# Pwrmon.net
KiCad netlist of a schematic drawn in EAGLE
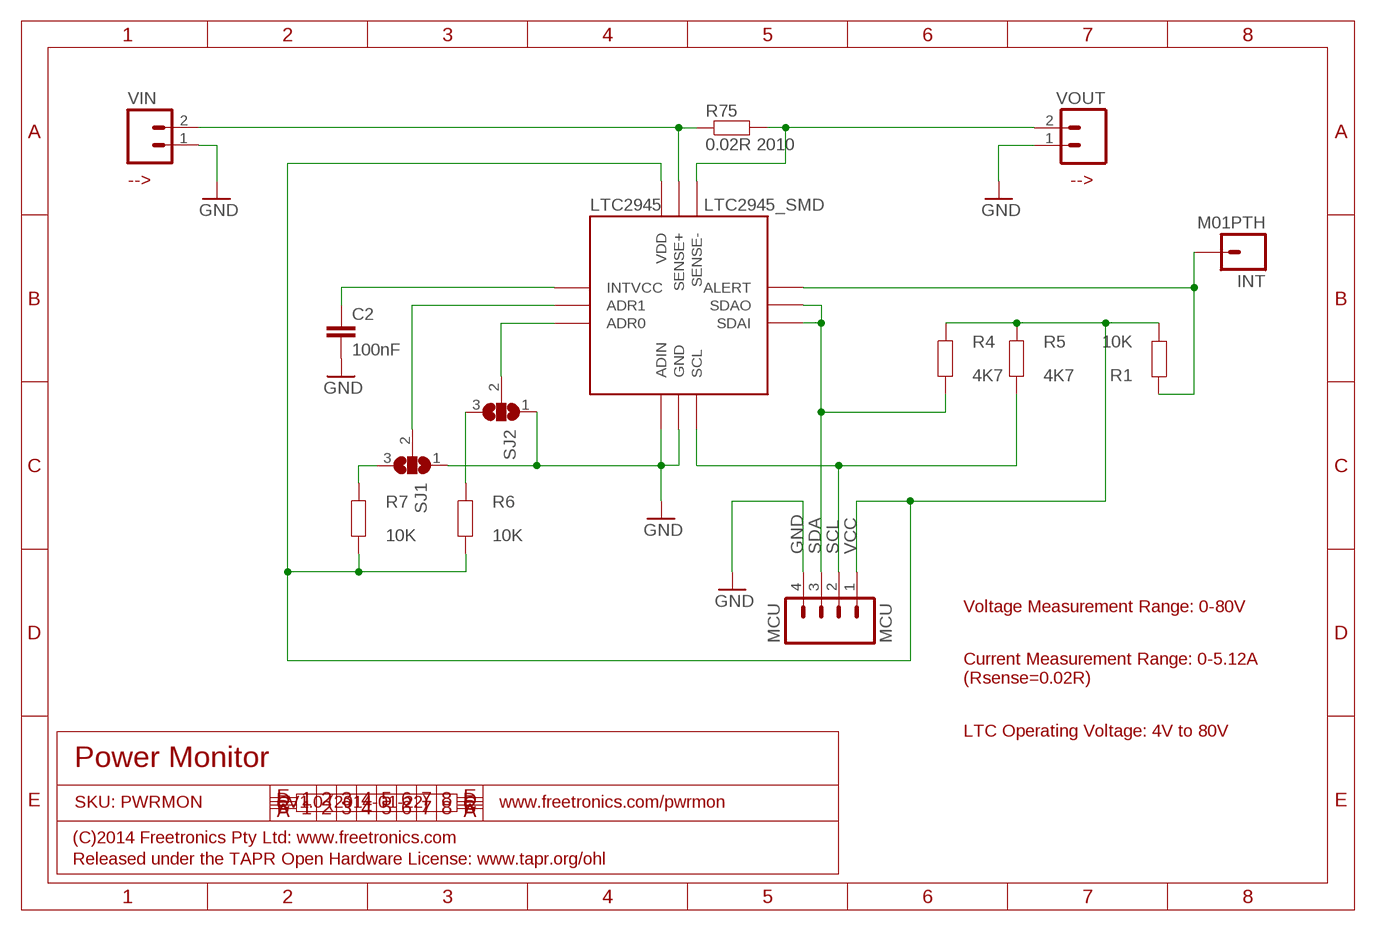
[diagram p0: schematic, sheet 1]

(export (version "E")
  (design (tool "Eeschema 10.0.6"))
  (components
    (comp (ref "C2")
      (value "100nF")
      (footprint "eagle-import:0603")
      (libsource (lib "eagle-import") (part "CAP0603"))
    )
    (comp (ref "INT")
      (value "M01PTH")
      (footprint "eagle-import:1X01")
      (libsource (lib "eagle-import") (part "M01PTH"))
    )
    (comp (ref "LTC2945")
      (value "LTC2945_SMD")
      (footprint "eagle-import:QFN-12")
      (libsource (lib "eagle-import") (part "LTC2945_SMD"))
    )
    (comp (ref "MCU")
      (value "MCU")
      (footprint "eagle-import:1X04")
      (libsource (lib "eagle-import") (part "M04PTH"))
    )
    (comp (ref "R1")
      (value "10K")
      (footprint "eagle-import:0603")
      (libsource (lib "eagle-import") (part "RESISTOR0603"))
    )
    (comp (ref "R4")
      (value "4K7")
      (footprint "eagle-import:0603")
      (libsource (lib "eagle-import") (part "RESISTOR0603"))
    )
    (comp (ref "R5")
      (value "4K7")
      (footprint "eagle-import:0603")
      (libsource (lib "eagle-import") (part "RESISTOR0603"))
    )
    (comp (ref "R6")
      (value "10K")
      (footprint "eagle-import:0603")
      (libsource (lib "eagle-import") (part "RESISTOR0603"))
    )
    (comp (ref "R7")
      (value "10K")
      (footprint "eagle-import:0603")
      (libsource (lib "eagle-import") (part "RESISTOR0603"))
    )
    (comp (ref "R75")
      (value "0.02R 2010")
      (footprint "eagle-import:R2010")
      (libsource (lib "eagle-import") (part "freetronics-original_RESISTOR2010"))
    )
    (comp (ref "SJ1")
      (value "SJ2W")
      (footprint "eagle-import:SJ_2")
      (libsource (lib "eagle-import") (part "SJ2W"))
    )
    (comp (ref "SJ2")
      (value "SJ2W")
      (footprint "eagle-import:SJ_2")
      (libsource (lib "eagle-import") (part "SJ2W"))
    )
    (comp (ref "VIN")
      (value "M02PTH")
      (footprint "eagle-import:1X02")
      (libsource (lib "eagle-import") (part "M02PTH"))
    )
    (comp (ref "VOUT")
      (value "M02PTH")
      (footprint "eagle-import:1X02")
      (libsource (lib "eagle-import") (part "M02PTH"))
    )
  )
  (nets
    (net (code "1") (name "/SCL") (class "Default")
      (node (ref "LTC2945") (pin "6") (pinfunction "SCL_6") (pintype "bidirectional"))
      (node (ref "MCU") (pin "2") (pinfunction "2_2") (pintype "passive"))
      (node (ref "R5") (pin "1") (pinfunction "1_1") (pintype "passive"))
    )
    (net (code "2") (name "/SDA") (class "Default")
      (node (ref "LTC2945") (pin "7") (pinfunction "SDAI_7") (pintype "bidirectional"))
      (node (ref "LTC2945") (pin "8") (pinfunction "SDAO_8") (pintype "bidirectional"))
      (node (ref "MCU") (pin "3") (pinfunction "3_3") (pintype "passive"))
      (node (ref "R4") (pin "1") (pinfunction "1_1") (pintype "passive"))
    )
    (net (code "3") (name "/VCC") (class "Default")
      (node (ref "LTC2945") (pin "12") (pinfunction "VDD_12") (pintype "bidirectional"))
      (node (ref "MCU") (pin "1") (pinfunction "1_1") (pintype "passive"))
      (node (ref "R1") (pin "1") (pinfunction "1_1") (pintype "passive"))
      (node (ref "R4") (pin "2") (pinfunction "2_2") (pintype "passive"))
      (node (ref "R5") (pin "2") (pinfunction "2_2") (pintype "passive"))
      (node (ref "R6") (pin "1") (pinfunction "1_1") (pintype "passive"))
      (node (ref "R7") (pin "1") (pinfunction "1_1") (pintype "passive"))
    )
    (net (code "4") (name "GND") (class "Default")
      (node (ref "C2") (pin "2") (pinfunction "2_2") (pintype "passive"))
      (node (ref "LTC2945") (pin "4") (pinfunction "ADIN_4") (pintype "bidirectional"))
      (node (ref "LTC2945") (pin "5") (pinfunction "GND_5") (pintype "bidirectional"))
      (node (ref "MCU") (pin "4") (pinfunction "4_4") (pintype "passive"))
      (node (ref "SJ1") (pin "1") (pinfunction "1_1") (pintype "passive"))
      (node (ref "SJ2") (pin "1") (pinfunction "1_1") (pintype "passive"))
      (node (ref "VIN") (pin "1") (pinfunction "1_1") (pintype "passive"))
      (node (ref "VOUT") (pin "1") (pinfunction "1_1") (pintype "passive"))
    )
    (net (code "5") (name "Net-(LTC2945-ADR0)") (class "Default")
      (node (ref "LTC2945") (pin "3") (pinfunction "ADR0_3") (pintype "bidirectional"))
      (node (ref "SJ2") (pin "2") (pinfunction "2_2") (pintype "passive"))
    )
    (net (code "6") (name "Net-(LTC2945-ADR1)") (class "Default")
      (node (ref "LTC2945") (pin "2") (pinfunction "ADR1_2") (pintype "bidirectional"))
      (node (ref "SJ1") (pin "2") (pinfunction "2_2") (pintype "passive"))
    )
    (net (code "7") (name "Net-(LTC2945-ALERT)") (class "Default")
      (node (ref "INT") (pin "1") (pinfunction "1_1") (pintype "passive"))
      (node (ref "LTC2945") (pin "9") (pinfunction "ALERT_9") (pintype "bidirectional"))
      (node (ref "R1") (pin "2") (pinfunction "2_2") (pintype "passive"))
    )
    (net (code "8") (name "Net-(LTC2945-INTVCC)") (class "Default")
      (node (ref "C2") (pin "1") (pinfunction "1_1") (pintype "passive"))
      (node (ref "LTC2945") (pin "1") (pinfunction "INTVCC_1") (pintype "bidirectional"))
    )
    (net (code "9") (name "Net-(LTC2945-SENSE+)") (class "Default")
      (node (ref "LTC2945") (pin "11") (pinfunction "SENSE+_11") (pintype "bidirectional"))
      (node (ref "R75") (pin "1") (pinfunction "1_1") (pintype "passive"))
      (node (ref "VIN") (pin "2") (pinfunction "2_2") (pintype "passive"))
    )
    (net (code "10") (name "Net-(LTC2945-SENSE-)") (class "Default")
      (node (ref "LTC2945") (pin "10") (pinfunction "SENSE-_10") (pintype "bidirectional"))
      (node (ref "R75") (pin "2") (pinfunction "2_2") (pintype "passive"))
      (node (ref "VOUT") (pin "2") (pinfunction "2_2") (pintype "passive"))
    )
    (net (code "11") (name "Net-(R6-Pad2)") (class "Default")
      (node (ref "R6") (pin "2") (pinfunction "2_2") (pintype "passive"))
      (node (ref "SJ2") (pin "3") (pinfunction "3_3") (pintype "passive"))
    )
    (net (code "12") (name "Net-(R7-Pad2)") (class "Default")
      (node (ref "R7") (pin "2") (pinfunction "2_2") (pintype "passive"))
      (node (ref "SJ1") (pin "3") (pinfunction "3_3") (pintype "passive"))
    )
  )
)
